# LTC3588_Board.net
KiCad netlist of a schematic drawn in EAGLE
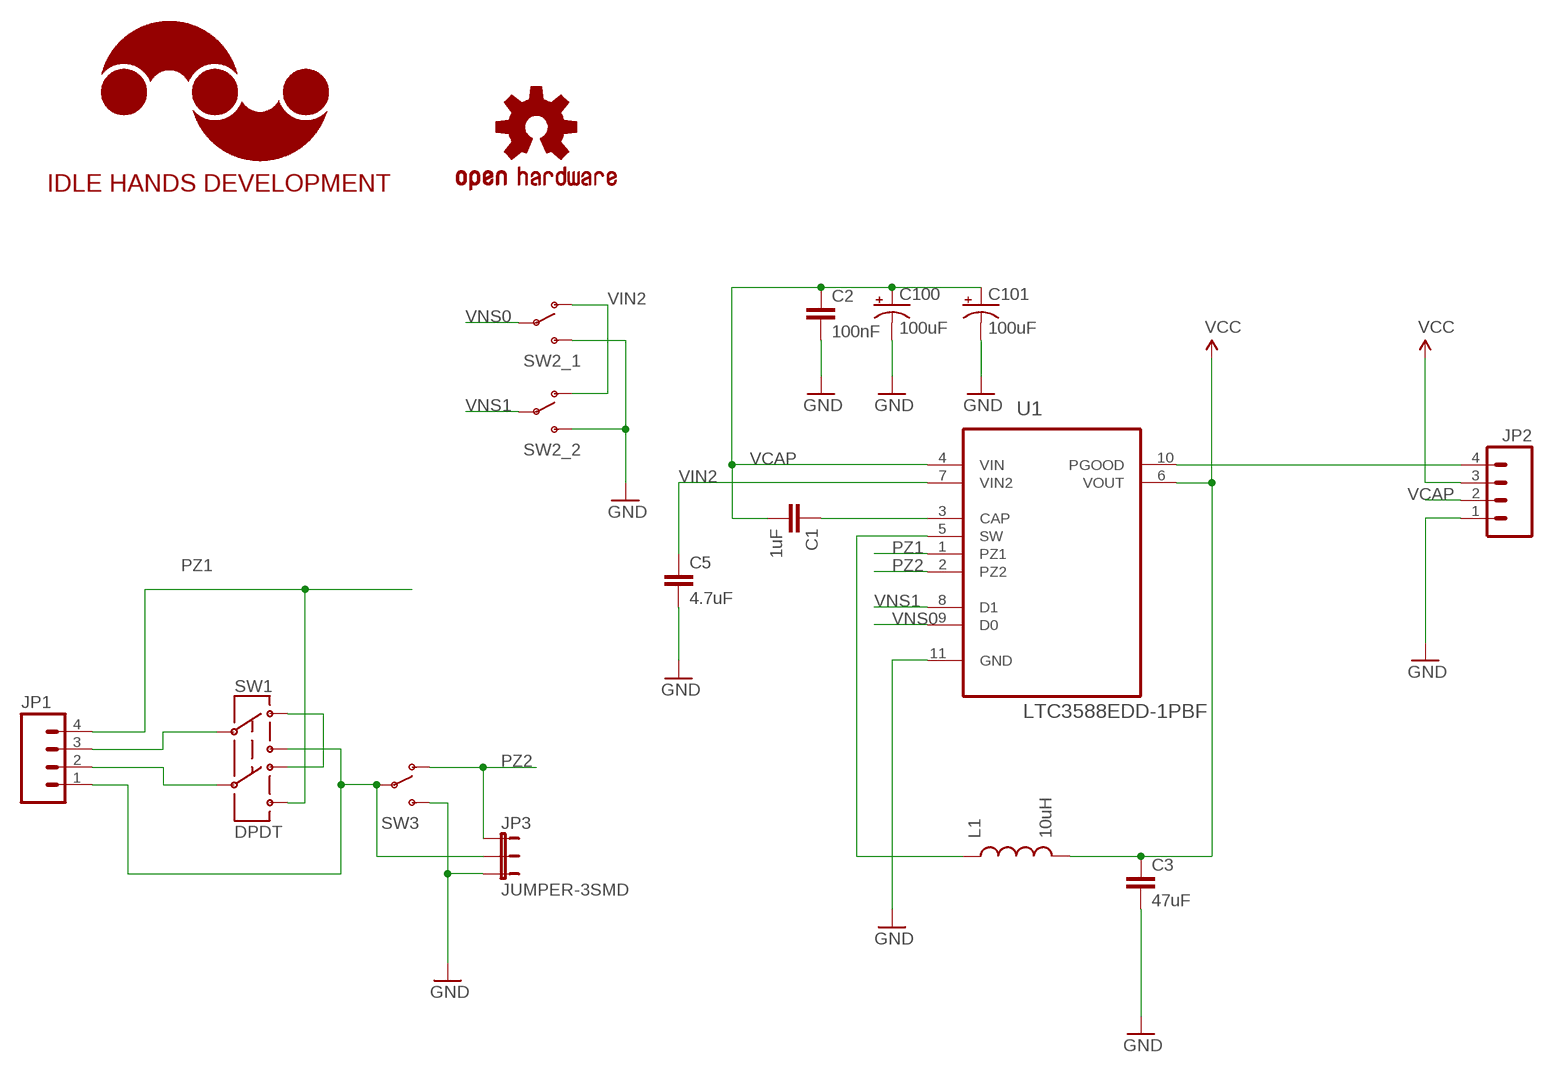
[diagram p0: schematic, sheet 1]

(export (version "E")
  (design (tool "Eeschema 10.0.6"))
  (components
    (comp (ref "C1")
      (value "1uF")
      (footprint "eagle-import:0603-CAP")
      (libsource (lib "eagle-import") (part "CAP0603-CAP"))
    )
    (comp (ref "C2")
      (value "100nF")
      (footprint "eagle-import:0603-CAP")
      (libsource (lib "eagle-import") (part "CAP0603-CAP"))
    )
    (comp (ref "C3")
      (value "47uF")
      (footprint "eagle-import:1206")
      (libsource (lib "eagle-import") (part "CAP1206"))
    )
    (comp (ref "C5")
      (value "4.7uF")
      (footprint "eagle-import:0603-CAP")
      (libsource (lib "eagle-import") (part "CAP0603-CAP"))
    )
    (comp (ref "C100")
      (value "100uF")
      (footprint "eagle-import:EIA7343")
      (libsource (lib "eagle-import") (part "CAP_POL7343"))
    )
    (comp (ref "C101")
      (value "100uF")
      (footprint "eagle-import:EIA7343")
      (libsource (lib "eagle-import") (part "CAP_POL7343"))
    )
    (comp (ref "JP1")
      (value "M04LOCK")
      (footprint "eagle-import:1X04_LOCK")
      (libsource (lib "eagle-import") (part "M04LOCK"))
    )
    (comp (ref "JP2")
      (value "M04LOCK")
      (footprint "eagle-import:1X04_LOCK")
      (libsource (lib "eagle-import") (part "M04LOCK"))
    )
    (comp (ref "JP3")
      (value "JUMPER-3SMD")
      (footprint "eagle-import:SJ_3")
      (libsource (lib "eagle-import") (part "JUMPER-3SMD"))
    )
    (comp (ref "L1")
      (value "10uH")
      (footprint "eagle-import:1210")
      (libsource (lib "eagle-import") (part "INDUCTOR1210"))
    )
    (comp (ref "LOGO1")
      (value "IDLEHANDS_LOGOS")
      (footprint "eagle-import:IHD-LOGO-S")
      (libsource (lib "eagle-import") (part "IDLEHANDS_LOGOS"))
    )
    (comp (ref "LOGO2")
      (value "OSHW-LOGOS")
      (footprint "eagle-import:OSHW-LOGO-S")
      (libsource (lib "eagle-import") (part "OSHW-LOGOS"))
    )
    (comp (ref "SW1")
      (value "DPDT")
      (footprint "eagle-import:AYZ0202")
      (libsource (lib "eagle-import") (part "SWITCH-DPDTAYZ0202"))
    )
    (comp (ref "SW2_1")
      (value "SWITCH-SPDT")
      (footprint "eagle-import:SWITCH-SPDT-SMD-CK")
      (libsource (lib "eagle-import") (part "SWITCH-SPDT"))
    )
    (comp (ref "SW2_2")
      (value "SWITCH-SPDT")
      (footprint "eagle-import:SWITCH-SPDT-SMD-CK")
      (libsource (lib "eagle-import") (part "SWITCH-SPDT"))
    )
    (comp (ref "SW3")
      (value "SWITCH-SPDT")
      (footprint "eagle-import:SWITCH-SPDT-SMD-CK")
      (libsource (lib "eagle-import") (part "SWITCH-SPDT"))
    )
    (comp (ref "U1")
      (value "LTC3588EDD-1PBF")
      (footprint "eagle-import:DFN300X300X80-11N")
      (fields (field (name "MPN") "LTC3588EDD-1#PBF"))
      (libsource (lib "eagle-import") (part "LTC3588EDD-1PBF"))
    )
  )
  (nets
    (net (code "1") (name "/PZ1") (class "Default")
      (node (ref "JP1") (pin "4") (pinfunction "4_4") (pintype "passive"))
      (node (ref "SW1") (pin "6") (pinfunction "6_6") (pintype "bidirectional"))
      (node (ref "U1") (pin "1") (pinfunction "PZ1_1") (pintype "input"))
    )
    (net (code "2") (name "/PZ2") (class "Default")
      (node (ref "JP3") (pin "1") (pinfunction "1_1") (pintype "passive"))
      (node (ref "SW3") (pin "1") (pinfunction "O_1") (pintype "passive"))
      (node (ref "U1") (pin "2") (pinfunction "PZ2_2") (pintype "input"))
    )
    (net (code "3") (name "/VCAP") (class "Default")
      (node (ref "C1") (pin "2") (pinfunction "2_2") (pintype "passive"))
      (node (ref "C100") (pin "A") (pinfunction "+_A") (pintype "passive"))
      (node (ref "C101") (pin "A") (pinfunction "+_A") (pintype "passive"))
      (node (ref "C2") (pin "1") (pinfunction "1_1") (pintype "passive"))
      (node (ref "JP2") (pin "2") (pinfunction "2_2") (pintype "passive"))
      (node (ref "U1") (pin "4") (pinfunction "VIN_4") (pintype "power_in"))
    )
    (net (code "4") (name "/VIN2") (class "Default")
      (node (ref "C5") (pin "1") (pinfunction "1_1") (pintype "passive"))
      (node (ref "SW2_1") (pin "1") (pinfunction "O_1") (pintype "passive"))
      (node (ref "SW2_2") (pin "1") (pinfunction "O_1") (pintype "passive"))
      (node (ref "U1") (pin "7") (pinfunction "VIN2_7") (pintype "power_in"))
    )
    (net (code "5") (name "/VNS0") (class "Default")
      (node (ref "SW2_1") (pin "2") (pinfunction "P_2") (pintype "passive"))
      (node (ref "U1") (pin "9") (pinfunction "D0_9") (pintype "input"))
    )
    (net (code "6") (name "/VNS1") (class "Default")
      (node (ref "SW2_2") (pin "2") (pinfunction "P_2") (pintype "passive"))
      (node (ref "U1") (pin "8") (pinfunction "D1_8") (pintype "input"))
    )
    (net (code "7") (name "GND") (class "Default")
      (node (ref "C100") (pin "C") (pinfunction "-_C") (pintype "passive"))
      (node (ref "C101") (pin "C") (pinfunction "-_C") (pintype "passive"))
      (node (ref "C2") (pin "2") (pinfunction "2_2") (pintype "passive"))
      (node (ref "C3") (pin "2") (pinfunction "2_2") (pintype "passive"))
      (node (ref "C5") (pin "2") (pinfunction "2_2") (pintype "passive"))
      (node (ref "JP2") (pin "1") (pinfunction "1_1") (pintype "passive"))
      (node (ref "JP3") (pin "3") (pinfunction "3_3") (pintype "passive"))
      (node (ref "SW2_1") (pin "3") (pinfunction "S_3") (pintype "passive"))
      (node (ref "SW2_2") (pin "3") (pinfunction "S_3") (pintype "passive"))
      (node (ref "SW3") (pin "3") (pinfunction "S_3") (pintype "passive"))
      (node (ref "U1") (pin "11") (pinfunction "GND_11") (pintype "passive"))
    )
    (net (code "8") (name "Net-(JP1-Pad2)") (class "Default")
      (node (ref "JP1") (pin "2") (pinfunction "2_2") (pintype "passive"))
      (node (ref "SW1") (pin "5") (pinfunction "5_5") (pintype "bidirectional"))
    )
    (net (code "9") (name "Net-(JP1-Pad3)") (class "Default")
      (node (ref "JP1") (pin "3") (pinfunction "3_3") (pintype "passive"))
      (node (ref "SW1") (pin "2") (pinfunction "2_2") (pintype "bidirectional"))
    )
    (net (code "10") (name "Net-(SW1-Pad1)") (class "Default")
      (node (ref "SW1") (pin "1") (pinfunction "1_1") (pintype "bidirectional"))
      (node (ref "SW1") (pin "4") (pinfunction "4_4") (pintype "bidirectional"))
    )
    (net (code "11") (name "Net-(SW3-P)") (class "Default")
      (node (ref "JP1") (pin "1") (pinfunction "1_1") (pintype "passive"))
      (node (ref "JP3") (pin "2") (pinfunction "2_2") (pintype "passive"))
      (node (ref "SW1") (pin "3") (pinfunction "3_3") (pintype "bidirectional"))
      (node (ref "SW3") (pin "2") (pinfunction "P_2") (pintype "passive"))
    )
    (net (code "12") (name "Net-(U1-CAP)") (class "Default")
      (node (ref "C1") (pin "1") (pinfunction "1_1") (pintype "passive"))
      (node (ref "U1") (pin "3") (pinfunction "CAP_3") (pintype "passive"))
    )
    (net (code "13") (name "Net-(U1-PGOOD)") (class "Default")
      (node (ref "JP2") (pin "4") (pinfunction "4_4") (pintype "passive"))
      (node (ref "U1") (pin "10") (pinfunction "PGOOD_10") (pintype "output"))
    )
    (net (code "14") (name "Net-(U1-SW)") (class "Default")
      (node (ref "L1") (pin "1") (pinfunction "1_1") (pintype "passive"))
      (node (ref "U1") (pin "5") (pinfunction "SW_5") (pintype "passive"))
    )
    (net (code "15") (name "VCC") (class "Default")
      (node (ref "C3") (pin "1") (pinfunction "1_1") (pintype "passive"))
      (node (ref "JP2") (pin "3") (pinfunction "3_3") (pintype "passive"))
      (node (ref "L1") (pin "2") (pinfunction "2_2") (pintype "passive"))
      (node (ref "U1") (pin "6") (pinfunction "VOUT_6") (pintype "output"))
    )
  )
)
